# dot-reader.net
KiCad netlist of a schematic drawn in EAGLE
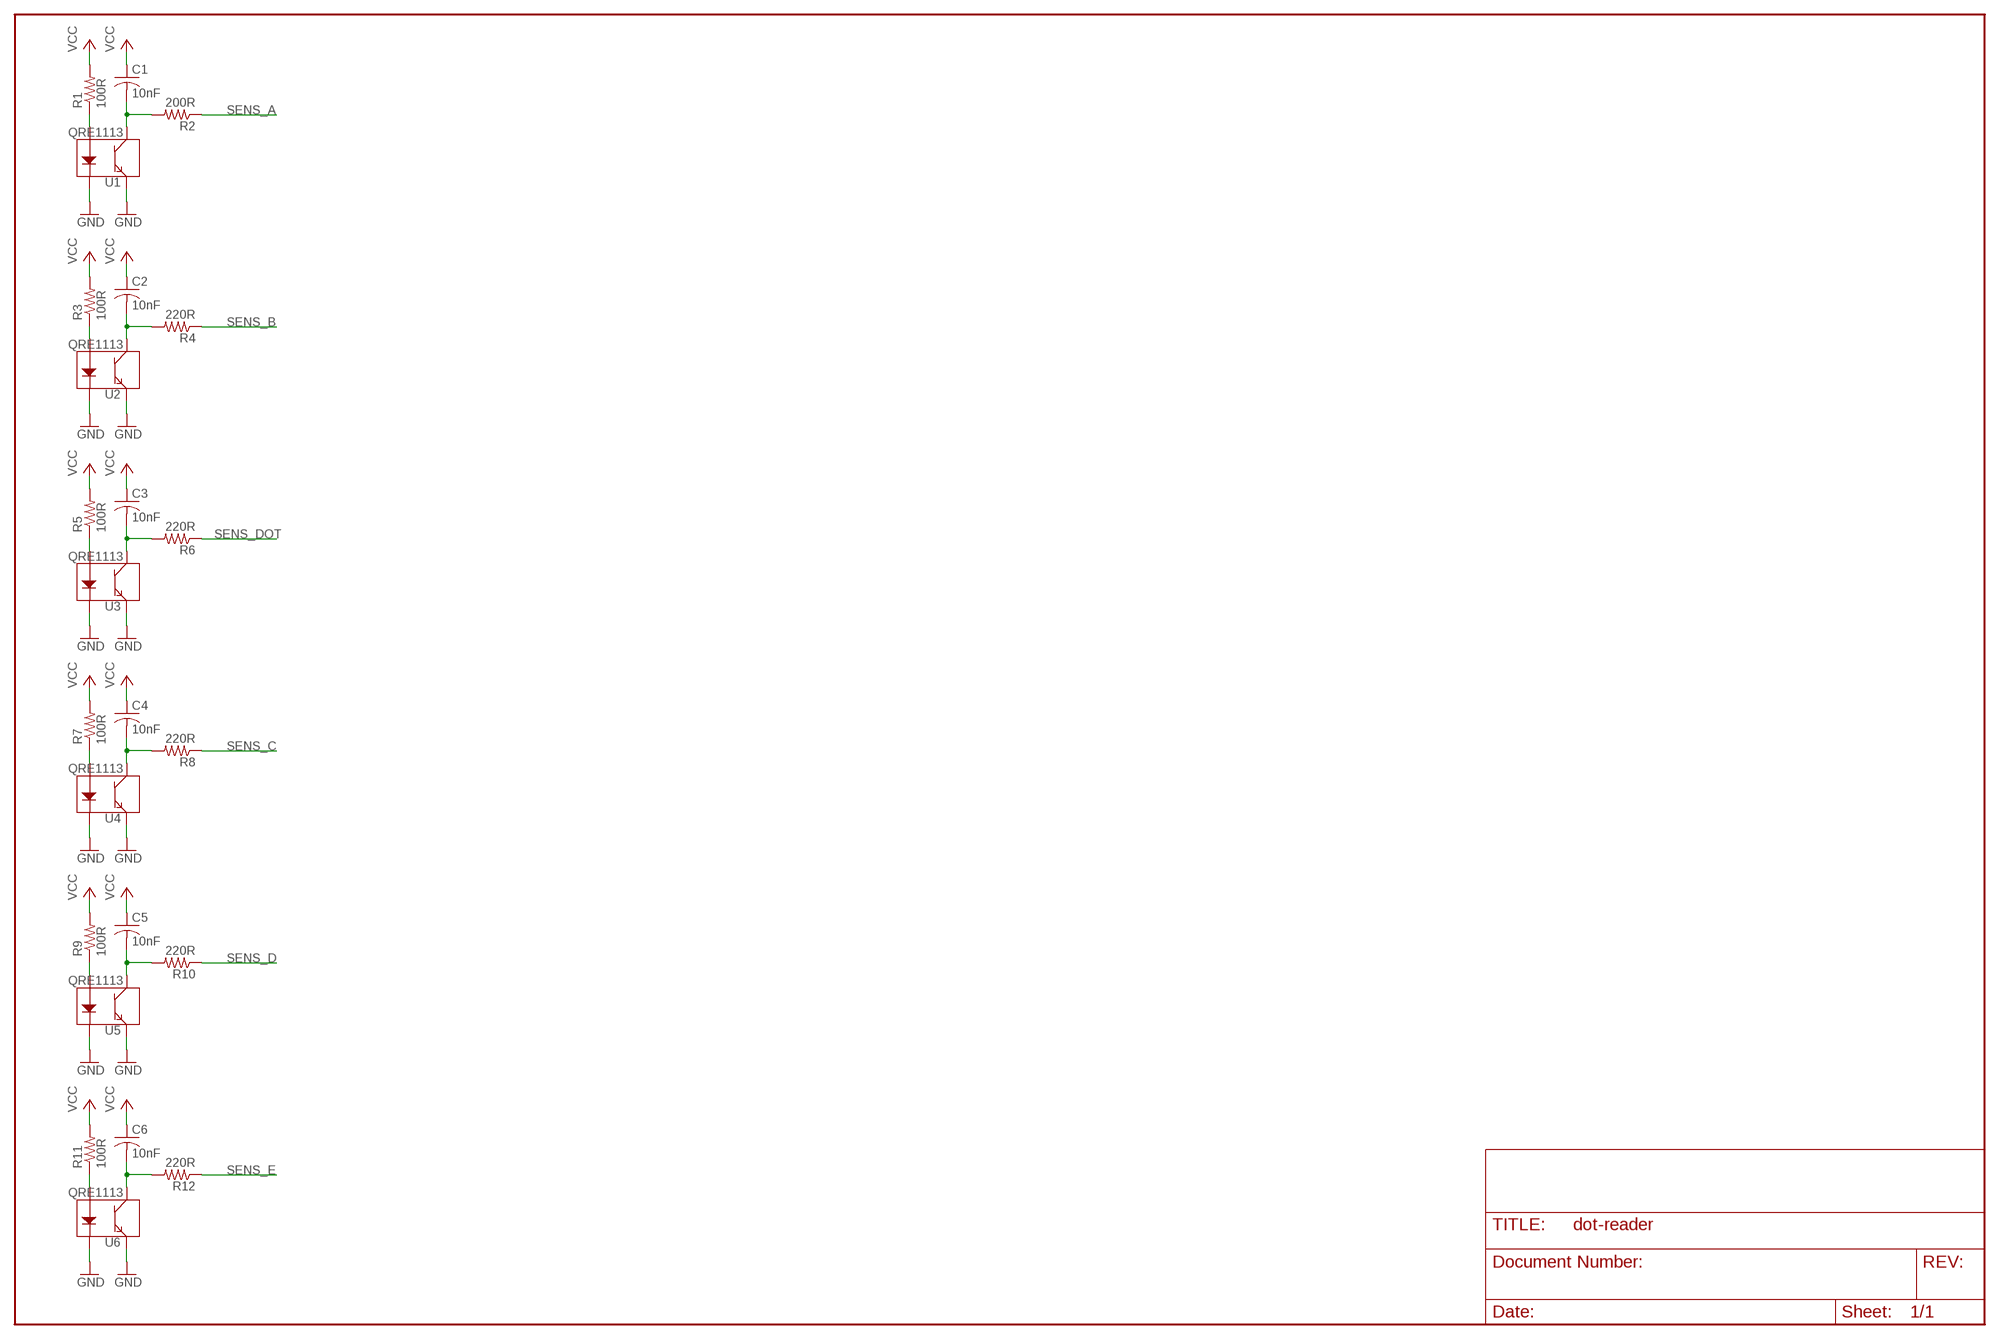
[diagram p0: schematic, sheet 1]

(export (version "E")
  (design (tool "Eeschema 10.0.6"))
  (components
    (comp (ref "C1")
      (value "10nF")
      (footprint "eagle-import:C0805")
      (libsource (lib "eagle-import") (part "C-USC0805"))
    )
    (comp (ref "C2")
      (value "10nF")
      (footprint "eagle-import:C0805")
      (libsource (lib "eagle-import") (part "C-USC0805"))
    )
    (comp (ref "C3")
      (value "10nF")
      (footprint "eagle-import:C0805")
      (libsource (lib "eagle-import") (part "C-USC0805"))
    )
    (comp (ref "C4")
      (value "10nF")
      (footprint "eagle-import:C0805")
      (libsource (lib "eagle-import") (part "C-USC0805"))
    )
    (comp (ref "C5")
      (value "10nF")
      (footprint "eagle-import:C0805")
      (libsource (lib "eagle-import") (part "C-USC0805"))
    )
    (comp (ref "C6")
      (value "10nF")
      (footprint "eagle-import:C0805")
      (libsource (lib "eagle-import") (part "C-USC0805"))
    )
    (comp (ref "R1")
      (value "100R")
      (footprint "eagle-import:M0805")
      (libsource (lib "eagle-import") (part "R-US_M0805"))
    )
    (comp (ref "R2")
      (value "200R")
      (footprint "eagle-import:M0805")
      (libsource (lib "eagle-import") (part "R-US_M0805"))
    )
    (comp (ref "R3")
      (value "100R")
      (footprint "eagle-import:M0805")
      (libsource (lib "eagle-import") (part "R-US_M0805"))
    )
    (comp (ref "R4")
      (value "220R")
      (footprint "eagle-import:M0805")
      (libsource (lib "eagle-import") (part "R-US_M0805"))
    )
    (comp (ref "R5")
      (value "100R")
      (footprint "eagle-import:M0805")
      (libsource (lib "eagle-import") (part "R-US_M0805"))
    )
    (comp (ref "R6")
      (value "220R")
      (footprint "eagle-import:M0805")
      (libsource (lib "eagle-import") (part "R-US_M0805"))
    )
    (comp (ref "R7")
      (value "100R")
      (footprint "eagle-import:M0805")
      (libsource (lib "eagle-import") (part "R-US_M0805"))
    )
    (comp (ref "R8")
      (value "220R")
      (footprint "eagle-import:M0805")
      (libsource (lib "eagle-import") (part "R-US_M0805"))
    )
    (comp (ref "R9")
      (value "100R")
      (footprint "eagle-import:M0805")
      (libsource (lib "eagle-import") (part "R-US_M0805"))
    )
    (comp (ref "R10")
      (value "220R")
      (footprint "eagle-import:M0805")
      (libsource (lib "eagle-import") (part "R-US_M0805"))
    )
    (comp (ref "R11")
      (value "100R")
      (footprint "eagle-import:M0805")
      (libsource (lib "eagle-import") (part "R-US_M0805"))
    )
    (comp (ref "R12")
      (value "220R")
      (footprint "eagle-import:M0805")
      (libsource (lib "eagle-import") (part "R-US_M0805"))
    )
    (comp (ref "U1")
      (value "QRE1113")
      (footprint "eagle-import:QRE1113")
      (libsource (lib "eagle-import") (part "QRE1113"))
    )
    (comp (ref "U2")
      (value "QRE1113")
      (footprint "eagle-import:QRE1113")
      (libsource (lib "eagle-import") (part "QRE1113"))
    )
    (comp (ref "U3")
      (value "QRE1113")
      (footprint "eagle-import:QRE1113")
      (libsource (lib "eagle-import") (part "QRE1113"))
    )
    (comp (ref "U4")
      (value "QRE1113")
      (footprint "eagle-import:QRE1113")
      (libsource (lib "eagle-import") (part "QRE1113"))
    )
    (comp (ref "U5")
      (value "QRE1113")
      (footprint "eagle-import:QRE1113")
      (libsource (lib "eagle-import") (part "QRE1113"))
    )
    (comp (ref "U6")
      (value "QRE1113")
      (footprint "eagle-import:QRE1113")
      (libsource (lib "eagle-import") (part "QRE1113"))
    )
  )
  (nets
    (net (code "1") (name "/SENS_A") (class "Default")
      (node (ref "R2") (pin "1") (pinfunction "1_1") (pintype "passive"))
    )
    (net (code "2") (name "/SENS_B") (class "Default")
      (node (ref "R4") (pin "1") (pinfunction "1_1") (pintype "passive"))
    )
    (net (code "3") (name "/SENS_C") (class "Default")
      (node (ref "R8") (pin "1") (pinfunction "1_1") (pintype "passive"))
    )
    (net (code "4") (name "/SENS_D") (class "Default")
      (node (ref "R10") (pin "1") (pinfunction "1_1") (pintype "passive"))
    )
    (net (code "5") (name "/SENS_DOT") (class "Default")
      (node (ref "R6") (pin "1") (pinfunction "1_1") (pintype "passive"))
    )
    (net (code "6") (name "/SENS_E") (class "Default")
      (node (ref "R12") (pin "1") (pinfunction "1_1") (pintype "passive"))
    )
    (net (code "7") (name "GND") (class "Default")
      (node (ref "U1") (pin "2") (pinfunction "K_2") (pintype "bidirectional"))
      (node (ref "U1") (pin "4") (pinfunction "E_4") (pintype "bidirectional"))
      (node (ref "U2") (pin "2") (pinfunction "K_2") (pintype "bidirectional"))
      (node (ref "U2") (pin "4") (pinfunction "E_4") (pintype "bidirectional"))
      (node (ref "U3") (pin "2") (pinfunction "K_2") (pintype "bidirectional"))
      (node (ref "U3") (pin "4") (pinfunction "E_4") (pintype "bidirectional"))
      (node (ref "U4") (pin "2") (pinfunction "K_2") (pintype "bidirectional"))
      (node (ref "U4") (pin "4") (pinfunction "E_4") (pintype "bidirectional"))
      (node (ref "U5") (pin "2") (pinfunction "K_2") (pintype "bidirectional"))
      (node (ref "U5") (pin "4") (pinfunction "E_4") (pintype "bidirectional"))
      (node (ref "U6") (pin "2") (pinfunction "K_2") (pintype "bidirectional"))
      (node (ref "U6") (pin "4") (pinfunction "E_4") (pintype "bidirectional"))
    )
    (net (code "8") (name "Net-(U1-A)") (class "Default")
      (node (ref "R1") (pin "1") (pinfunction "1_1") (pintype "passive"))
      (node (ref "U1") (pin "1") (pinfunction "A_1") (pintype "bidirectional"))
    )
    (net (code "9") (name "Net-(U1-C)") (class "Default")
      (node (ref "C1") (pin "2") (pinfunction "2_2") (pintype "passive"))
      (node (ref "R2") (pin "2") (pinfunction "2_2") (pintype "passive"))
      (node (ref "U1") (pin "3") (pinfunction "C_3") (pintype "bidirectional"))
    )
    (net (code "10") (name "Net-(U2-A)") (class "Default")
      (node (ref "R3") (pin "1") (pinfunction "1_1") (pintype "passive"))
      (node (ref "U2") (pin "1") (pinfunction "A_1") (pintype "bidirectional"))
    )
    (net (code "11") (name "Net-(U2-C)") (class "Default")
      (node (ref "C2") (pin "2") (pinfunction "2_2") (pintype "passive"))
      (node (ref "R4") (pin "2") (pinfunction "2_2") (pintype "passive"))
      (node (ref "U2") (pin "3") (pinfunction "C_3") (pintype "bidirectional"))
    )
    (net (code "12") (name "Net-(U3-A)") (class "Default")
      (node (ref "R5") (pin "1") (pinfunction "1_1") (pintype "passive"))
      (node (ref "U3") (pin "1") (pinfunction "A_1") (pintype "bidirectional"))
    )
    (net (code "13") (name "Net-(U3-C)") (class "Default")
      (node (ref "C3") (pin "2") (pinfunction "2_2") (pintype "passive"))
      (node (ref "R6") (pin "2") (pinfunction "2_2") (pintype "passive"))
      (node (ref "U3") (pin "3") (pinfunction "C_3") (pintype "bidirectional"))
    )
    (net (code "14") (name "Net-(U4-A)") (class "Default")
      (node (ref "R7") (pin "1") (pinfunction "1_1") (pintype "passive"))
      (node (ref "U4") (pin "1") (pinfunction "A_1") (pintype "bidirectional"))
    )
    (net (code "15") (name "Net-(U4-C)") (class "Default")
      (node (ref "C4") (pin "2") (pinfunction "2_2") (pintype "passive"))
      (node (ref "R8") (pin "2") (pinfunction "2_2") (pintype "passive"))
      (node (ref "U4") (pin "3") (pinfunction "C_3") (pintype "bidirectional"))
    )
    (net (code "16") (name "Net-(U5-A)") (class "Default")
      (node (ref "R9") (pin "1") (pinfunction "1_1") (pintype "passive"))
      (node (ref "U5") (pin "1") (pinfunction "A_1") (pintype "bidirectional"))
    )
    (net (code "17") (name "Net-(U5-C)") (class "Default")
      (node (ref "C5") (pin "2") (pinfunction "2_2") (pintype "passive"))
      (node (ref "R10") (pin "2") (pinfunction "2_2") (pintype "passive"))
      (node (ref "U5") (pin "3") (pinfunction "C_3") (pintype "bidirectional"))
    )
    (net (code "18") (name "Net-(U6-A)") (class "Default")
      (node (ref "R11") (pin "1") (pinfunction "1_1") (pintype "passive"))
      (node (ref "U6") (pin "1") (pinfunction "A_1") (pintype "bidirectional"))
    )
    (net (code "19") (name "Net-(U6-C)") (class "Default")
      (node (ref "C6") (pin "2") (pinfunction "2_2") (pintype "passive"))
      (node (ref "R12") (pin "2") (pinfunction "2_2") (pintype "passive"))
      (node (ref "U6") (pin "3") (pinfunction "C_3") (pintype "bidirectional"))
    )
    (net (code "20") (name "VCC") (class "Default")
      (node (ref "C1") (pin "1") (pinfunction "1_1") (pintype "passive"))
      (node (ref "C2") (pin "1") (pinfunction "1_1") (pintype "passive"))
      (node (ref "C3") (pin "1") (pinfunction "1_1") (pintype "passive"))
      (node (ref "C4") (pin "1") (pinfunction "1_1") (pintype "passive"))
      (node (ref "C5") (pin "1") (pinfunction "1_1") (pintype "passive"))
      (node (ref "C6") (pin "1") (pinfunction "1_1") (pintype "passive"))
      (node (ref "R1") (pin "2") (pinfunction "2_2") (pintype "passive"))
      (node (ref "R11") (pin "2") (pinfunction "2_2") (pintype "passive"))
      (node (ref "R3") (pin "2") (pinfunction "2_2") (pintype "passive"))
      (node (ref "R5") (pin "2") (pinfunction "2_2") (pintype "passive"))
      (node (ref "R7") (pin "2") (pinfunction "2_2") (pintype "passive"))
      (node (ref "R9") (pin "2") (pinfunction "2_2") (pintype "passive"))
    )
  )
)
